# Adafruit_IS31FL3731_CharliePlex_Grid.net
KiCad netlist of a schematic drawn in EAGLE
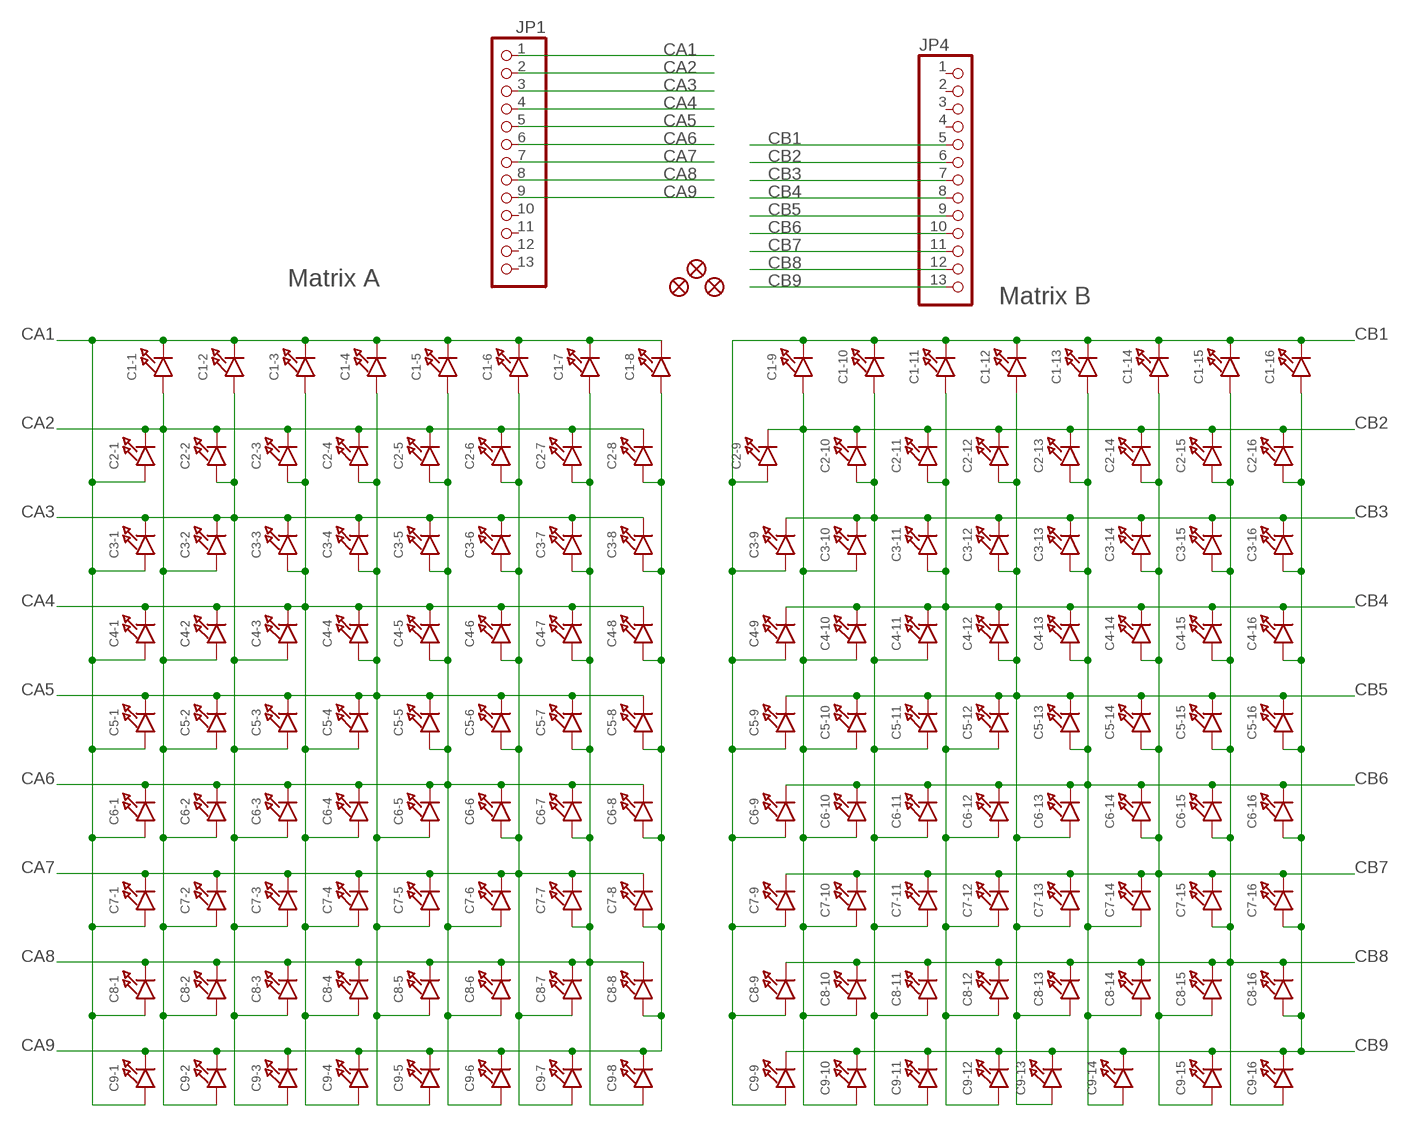
[diagram p0: schematic, sheet 1]

(export (version "E")
  (design (tool "Eeschema 10.0.6"))
  (components
    (comp (ref "C1-1")
      (value "LED0603_NOOUTLINE")
      (footprint "eagle-import:CHIPLED_0603_NOOUTLINE")
      (libsource (lib "eagle-import") (part "LED0603_NOOUTLINE"))
    )
    (comp (ref "C1-2")
      (value "LED0603_NOOUTLINE")
      (footprint "eagle-import:CHIPLED_0603_NOOUTLINE")
      (libsource (lib "eagle-import") (part "LED0603_NOOUTLINE"))
    )
    (comp (ref "C1-3")
      (value "LED0603_NOOUTLINE")
      (footprint "eagle-import:CHIPLED_0603_NOOUTLINE")
      (libsource (lib "eagle-import") (part "LED0603_NOOUTLINE"))
    )
    (comp (ref "C1-4")
      (value "LED0603_NOOUTLINE")
      (footprint "eagle-import:CHIPLED_0603_NOOUTLINE")
      (libsource (lib "eagle-import") (part "LED0603_NOOUTLINE"))
    )
    (comp (ref "C1-5")
      (value "LED0603_NOOUTLINE")
      (footprint "eagle-import:CHIPLED_0603_NOOUTLINE")
      (libsource (lib "eagle-import") (part "LED0603_NOOUTLINE"))
    )
    (comp (ref "C1-6")
      (value "LED0603_NOOUTLINE")
      (footprint "eagle-import:CHIPLED_0603_NOOUTLINE")
      (libsource (lib "eagle-import") (part "LED0603_NOOUTLINE"))
    )
    (comp (ref "C1-7")
      (value "LED0603_NOOUTLINE")
      (footprint "eagle-import:CHIPLED_0603_NOOUTLINE")
      (libsource (lib "eagle-import") (part "LED0603_NOOUTLINE"))
    )
    (comp (ref "C1-8")
      (value "LED0603_NOOUTLINE")
      (footprint "eagle-import:CHIPLED_0603_NOOUTLINE")
      (libsource (lib "eagle-import") (part "LED0603_NOOUTLINE"))
    )
    (comp (ref "C1-9")
      (value "LED0603_NOOUTLINE")
      (footprint "eagle-import:CHIPLED_0603_NOOUTLINE")
      (libsource (lib "eagle-import") (part "LED0603_NOOUTLINE"))
    )
    (comp (ref "C1-10")
      (value "LED0603_NOOUTLINE")
      (footprint "eagle-import:CHIPLED_0603_NOOUTLINE")
      (libsource (lib "eagle-import") (part "LED0603_NOOUTLINE"))
    )
    (comp (ref "C1-11")
      (value "LED0603_NOOUTLINE")
      (footprint "eagle-import:CHIPLED_0603_NOOUTLINE")
      (libsource (lib "eagle-import") (part "LED0603_NOOUTLINE"))
    )
    (comp (ref "C1-12")
      (value "LED0603_NOOUTLINE")
      (footprint "eagle-import:CHIPLED_0603_NOOUTLINE")
      (libsource (lib "eagle-import") (part "LED0603_NOOUTLINE"))
    )
    (comp (ref "C1-13")
      (value "LED0603_NOOUTLINE")
      (footprint "eagle-import:CHIPLED_0603_NOOUTLINE")
      (libsource (lib "eagle-import") (part "LED0603_NOOUTLINE"))
    )
    (comp (ref "C1-14")
      (value "LED0603_NOOUTLINE")
      (footprint "eagle-import:CHIPLED_0603_NOOUTLINE")
      (libsource (lib "eagle-import") (part "LED0603_NOOUTLINE"))
    )
    (comp (ref "C1-15")
      (value "LED0603_NOOUTLINE")
      (footprint "eagle-import:CHIPLED_0603_NOOUTLINE")
      (libsource (lib "eagle-import") (part "LED0603_NOOUTLINE"))
    )
    (comp (ref "C1-16")
      (value "LED0603_NOOUTLINE")
      (footprint "eagle-import:CHIPLED_0603_NOOUTLINE")
      (libsource (lib "eagle-import") (part "LED0603_NOOUTLINE"))
    )
    (comp (ref "C2-1")
      (value "LED0603_NOOUTLINE")
      (footprint "eagle-import:CHIPLED_0603_NOOUTLINE")
      (libsource (lib "eagle-import") (part "LED0603_NOOUTLINE"))
    )
    (comp (ref "C2-2")
      (value "LED0603_NOOUTLINE")
      (footprint "eagle-import:CHIPLED_0603_NOOUTLINE")
      (libsource (lib "eagle-import") (part "LED0603_NOOUTLINE"))
    )
    (comp (ref "C2-3")
      (value "LED0603_NOOUTLINE")
      (footprint "eagle-import:CHIPLED_0603_NOOUTLINE")
      (libsource (lib "eagle-import") (part "LED0603_NOOUTLINE"))
    )
    (comp (ref "C2-4")
      (value "LED0603_NOOUTLINE")
      (footprint "eagle-import:CHIPLED_0603_NOOUTLINE")
      (libsource (lib "eagle-import") (part "LED0603_NOOUTLINE"))
    )
    (comp (ref "C2-5")
      (value "LED0603_NOOUTLINE")
      (footprint "eagle-import:CHIPLED_0603_NOOUTLINE")
      (libsource (lib "eagle-import") (part "LED0603_NOOUTLINE"))
    )
    (comp (ref "C2-6")
      (value "LED0603_NOOUTLINE")
      (footprint "eagle-import:CHIPLED_0603_NOOUTLINE")
      (libsource (lib "eagle-import") (part "LED0603_NOOUTLINE"))
    )
    (comp (ref "C2-7")
      (value "LED0603_NOOUTLINE")
      (footprint "eagle-import:CHIPLED_0603_NOOUTLINE")
      (libsource (lib "eagle-import") (part "LED0603_NOOUTLINE"))
    )
    (comp (ref "C2-8")
      (value "LED0603_NOOUTLINE")
      (footprint "eagle-import:CHIPLED_0603_NOOUTLINE")
      (libsource (lib "eagle-import") (part "LED0603_NOOUTLINE"))
    )
    (comp (ref "C2-9")
      (value "LED0603_NOOUTLINE")
      (footprint "eagle-import:CHIPLED_0603_NOOUTLINE")
      (libsource (lib "eagle-import") (part "LED0603_NOOUTLINE"))
    )
    (comp (ref "C2-10")
      (value "LED0603_NOOUTLINE")
      (footprint "eagle-import:CHIPLED_0603_NOOUTLINE")
      (libsource (lib "eagle-import") (part "LED0603_NOOUTLINE"))
    )
    (comp (ref "C2-11")
      (value "LED0603_NOOUTLINE")
      (footprint "eagle-import:CHIPLED_0603_NOOUTLINE")
      (libsource (lib "eagle-import") (part "LED0603_NOOUTLINE"))
    )
    (comp (ref "C2-12")
      (value "LED0603_NOOUTLINE")
      (footprint "eagle-import:CHIPLED_0603_NOOUTLINE")
      (libsource (lib "eagle-import") (part "LED0603_NOOUTLINE"))
    )
    (comp (ref "C2-13")
      (value "LED0603_NOOUTLINE")
      (footprint "eagle-import:CHIPLED_0603_NOOUTLINE")
      (libsource (lib "eagle-import") (part "LED0603_NOOUTLINE"))
    )
    (comp (ref "C2-14")
      (value "LED0603_NOOUTLINE")
      (footprint "eagle-import:CHIPLED_0603_NOOUTLINE")
      (libsource (lib "eagle-import") (part "LED0603_NOOUTLINE"))
    )
    (comp (ref "C2-15")
      (value "LED0603_NOOUTLINE")
      (footprint "eagle-import:CHIPLED_0603_NOOUTLINE")
      (libsource (lib "eagle-import") (part "LED0603_NOOUTLINE"))
    )
    (comp (ref "C2-16")
      (value "LED0603_NOOUTLINE")
      (footprint "eagle-import:CHIPLED_0603_NOOUTLINE")
      (libsource (lib "eagle-import") (part "LED0603_NOOUTLINE"))
    )
    (comp (ref "C3-1")
      (value "LED0603_NOOUTLINE")
      (footprint "eagle-import:CHIPLED_0603_NOOUTLINE")
      (libsource (lib "eagle-import") (part "LED0603_NOOUTLINE"))
    )
    (comp (ref "C3-2")
      (value "LED0603_NOOUTLINE")
      (footprint "eagle-import:CHIPLED_0603_NOOUTLINE")
      (libsource (lib "eagle-import") (part "LED0603_NOOUTLINE"))
    )
    (comp (ref "C3-3")
      (value "LED0603_NOOUTLINE")
      (footprint "eagle-import:CHIPLED_0603_NOOUTLINE")
      (libsource (lib "eagle-import") (part "LED0603_NOOUTLINE"))
    )
    (comp (ref "C3-4")
      (value "LED0603_NOOUTLINE")
      (footprint "eagle-import:CHIPLED_0603_NOOUTLINE")
      (libsource (lib "eagle-import") (part "LED0603_NOOUTLINE"))
    )
    (comp (ref "C3-5")
      (value "LED0603_NOOUTLINE")
      (footprint "eagle-import:CHIPLED_0603_NOOUTLINE")
      (libsource (lib "eagle-import") (part "LED0603_NOOUTLINE"))
    )
    (comp (ref "C3-6")
      (value "LED0603_NOOUTLINE")
      (footprint "eagle-import:CHIPLED_0603_NOOUTLINE")
      (libsource (lib "eagle-import") (part "LED0603_NOOUTLINE"))
    )
    (comp (ref "C3-7")
      (value "LED0603_NOOUTLINE")
      (footprint "eagle-import:CHIPLED_0603_NOOUTLINE")
      (libsource (lib "eagle-import") (part "LED0603_NOOUTLINE"))
    )
    (comp (ref "C3-8")
      (value "LED0603_NOOUTLINE")
      (footprint "eagle-import:CHIPLED_0603_NOOUTLINE")
      (libsource (lib "eagle-import") (part "LED0603_NOOUTLINE"))
    )
    (comp (ref "C3-9")
      (value "LED0603_NOOUTLINE")
      (footprint "eagle-import:CHIPLED_0603_NOOUTLINE")
      (libsource (lib "eagle-import") (part "LED0603_NOOUTLINE"))
    )
    (comp (ref "C3-10")
      (value "LED0603_NOOUTLINE")
      (footprint "eagle-import:CHIPLED_0603_NOOUTLINE")
      (libsource (lib "eagle-import") (part "LED0603_NOOUTLINE"))
    )
    (comp (ref "C3-11")
      (value "LED0603_NOOUTLINE")
      (footprint "eagle-import:CHIPLED_0603_NOOUTLINE")
      (libsource (lib "eagle-import") (part "LED0603_NOOUTLINE"))
    )
    (comp (ref "C3-12")
      (value "LED0603_NOOUTLINE")
      (footprint "eagle-import:CHIPLED_0603_NOOUTLINE")
      (libsource (lib "eagle-import") (part "LED0603_NOOUTLINE"))
    )
    (comp (ref "C3-13")
      (value "LED0603_NOOUTLINE")
      (footprint "eagle-import:CHIPLED_0603_NOOUTLINE")
      (libsource (lib "eagle-import") (part "LED0603_NOOUTLINE"))
    )
    (comp (ref "C3-14")
      (value "LED0603_NOOUTLINE")
      (footprint "eagle-import:CHIPLED_0603_NOOUTLINE")
      (libsource (lib "eagle-import") (part "LED0603_NOOUTLINE"))
    )
    (comp (ref "C3-15")
      (value "LED0603_NOOUTLINE")
      (footprint "eagle-import:CHIPLED_0603_NOOUTLINE")
      (libsource (lib "eagle-import") (part "LED0603_NOOUTLINE"))
    )
    (comp (ref "C3-16")
      (value "LED0603_NOOUTLINE")
      (footprint "eagle-import:CHIPLED_0603_NOOUTLINE")
      (libsource (lib "eagle-import") (part "LED0603_NOOUTLINE"))
    )
    (comp (ref "C4-1")
      (value "LED0603_NOOUTLINE")
      (footprint "eagle-import:CHIPLED_0603_NOOUTLINE")
      (libsource (lib "eagle-import") (part "LED0603_NOOUTLINE"))
    )
    (comp (ref "C4-2")
      (value "LED0603_NOOUTLINE")
      (footprint "eagle-import:CHIPLED_0603_NOOUTLINE")
      (libsource (lib "eagle-import") (part "LED0603_NOOUTLINE"))
    )
    (comp (ref "C4-3")
      (value "LED0603_NOOUTLINE")
      (footprint "eagle-import:CHIPLED_0603_NOOUTLINE")
      (libsource (lib "eagle-import") (part "LED0603_NOOUTLINE"))
    )
    (comp (ref "C4-4")
      (value "LED0603_NOOUTLINE")
      (footprint "eagle-import:CHIPLED_0603_NOOUTLINE")
      (libsource (lib "eagle-import") (part "LED0603_NOOUTLINE"))
    )
    (comp (ref "C4-5")
      (value "LED0603_NOOUTLINE")
      (footprint "eagle-import:CHIPLED_0603_NOOUTLINE")
      (libsource (lib "eagle-import") (part "LED0603_NOOUTLINE"))
    )
    (comp (ref "C4-6")
      (value "LED0603_NOOUTLINE")
      (footprint "eagle-import:CHIPLED_0603_NOOUTLINE")
      (libsource (lib "eagle-import") (part "LED0603_NOOUTLINE"))
    )
    (comp (ref "C4-7")
      (value "LED0603_NOOUTLINE")
      (footprint "eagle-import:CHIPLED_0603_NOOUTLINE")
      (libsource (lib "eagle-import") (part "LED0603_NOOUTLINE"))
    )
    (comp (ref "C4-8")
      (value "LED0603_NOOUTLINE")
      (footprint "eagle-import:CHIPLED_0603_NOOUTLINE")
      (libsource (lib "eagle-import") (part "LED0603_NOOUTLINE"))
    )
    (comp (ref "C4-9")
      (value "LED0603_NOOUTLINE")
      (footprint "eagle-import:CHIPLED_0603_NOOUTLINE")
      (libsource (lib "eagle-import") (part "LED0603_NOOUTLINE"))
    )
    (comp (ref "C4-10")
      (value "LED0603_NOOUTLINE")
      (footprint "eagle-import:CHIPLED_0603_NOOUTLINE")
      (libsource (lib "eagle-import") (part "LED0603_NOOUTLINE"))
    )
    (comp (ref "C4-11")
      (value "LED0603_NOOUTLINE")
      (footprint "eagle-import:CHIPLED_0603_NOOUTLINE")
      (libsource (lib "eagle-import") (part "LED0603_NOOUTLINE"))
    )
    (comp (ref "C4-12")
      (value "LED0603_NOOUTLINE")
      (footprint "eagle-import:CHIPLED_0603_NOOUTLINE")
      (libsource (lib "eagle-import") (part "LED0603_NOOUTLINE"))
    )
    (comp (ref "C4-13")
      (value "LED0603_NOOUTLINE")
      (footprint "eagle-import:CHIPLED_0603_NOOUTLINE")
      (libsource (lib "eagle-import") (part "LED0603_NOOUTLINE"))
    )
    (comp (ref "C4-14")
      (value "LED0603_NOOUTLINE")
      (footprint "eagle-import:CHIPLED_0603_NOOUTLINE")
      (libsource (lib "eagle-import") (part "LED0603_NOOUTLINE"))
    )
    (comp (ref "C4-15")
      (value "LED0603_NOOUTLINE")
      (footprint "eagle-import:CHIPLED_0603_NOOUTLINE")
      (libsource (lib "eagle-import") (part "LED0603_NOOUTLINE"))
    )
    (comp (ref "C4-16")
      (value "LED0603_NOOUTLINE")
      (footprint "eagle-import:CHIPLED_0603_NOOUTLINE")
      (libsource (lib "eagle-import") (part "LED0603_NOOUTLINE"))
    )
    (comp (ref "C5-1")
      (value "LED0603_NOOUTLINE")
      (footprint "eagle-import:CHIPLED_0603_NOOUTLINE")
      (libsource (lib "eagle-import") (part "LED0603_NOOUTLINE"))
    )
    (comp (ref "C5-2")
      (value "LED0603_NOOUTLINE")
      (footprint "eagle-import:CHIPLED_0603_NOOUTLINE")
      (libsource (lib "eagle-import") (part "LED0603_NOOUTLINE"))
    )
    (comp (ref "C5-3")
      (value "LED0603_NOOUTLINE")
      (footprint "eagle-import:CHIPLED_0603_NOOUTLINE")
      (libsource (lib "eagle-import") (part "LED0603_NOOUTLINE"))
    )
    (comp (ref "C5-4")
      (value "LED0603_NOOUTLINE")
      (footprint "eagle-import:CHIPLED_0603_NOOUTLINE")
      (libsource (lib "eagle-import") (part "LED0603_NOOUTLINE"))
    )
    (comp (ref "C5-5")
      (value "LED0603_NOOUTLINE")
      (footprint "eagle-import:CHIPLED_0603_NOOUTLINE")
      (libsource (lib "eagle-import") (part "LED0603_NOOUTLINE"))
    )
    (comp (ref "C5-6")
      (value "LED0603_NOOUTLINE")
      (footprint "eagle-import:CHIPLED_0603_NOOUTLINE")
      (libsource (lib "eagle-import") (part "LED0603_NOOUTLINE"))
    )
    (comp (ref "C5-7")
      (value "LED0603_NOOUTLINE")
      (footprint "eagle-import:CHIPLED_0603_NOOUTLINE")
      (libsource (lib "eagle-import") (part "LED0603_NOOUTLINE"))
    )
    (comp (ref "C5-8")
      (value "LED0603_NOOUTLINE")
      (footprint "eagle-import:CHIPLED_0603_NOOUTLINE")
      (libsource (lib "eagle-import") (part "LED0603_NOOUTLINE"))
    )
    (comp (ref "C5-9")
      (value "LED0603_NOOUTLINE")
      (footprint "eagle-import:CHIPLED_0603_NOOUTLINE")
      (libsource (lib "eagle-import") (part "LED0603_NOOUTLINE"))
    )
    (comp (ref "C5-10")
      (value "LED0603_NOOUTLINE")
      (footprint "eagle-import:CHIPLED_0603_NOOUTLINE")
      (libsource (lib "eagle-import") (part "LED0603_NOOUTLINE"))
    )
    (comp (ref "C5-11")
      (value "LED0603_NOOUTLINE")
      (footprint "eagle-import:CHIPLED_0603_NOOUTLINE")
      (libsource (lib "eagle-import") (part "LED0603_NOOUTLINE"))
    )
    (comp (ref "C5-12")
      (value "LED0603_NOOUTLINE")
      (footprint "eagle-import:CHIPLED_0603_NOOUTLINE")
      (libsource (lib "eagle-import") (part "LED0603_NOOUTLINE"))
    )
    (comp (ref "C5-13")
      (value "LED0603_NOOUTLINE")
      (footprint "eagle-import:CHIPLED_0603_NOOUTLINE")
      (libsource (lib "eagle-import") (part "LED0603_NOOUTLINE"))
    )
    (comp (ref "C5-14")
      (value "LED0603_NOOUTLINE")
      (footprint "eagle-import:CHIPLED_0603_NOOUTLINE")
      (libsource (lib "eagle-import") (part "LED0603_NOOUTLINE"))
    )
    (comp (ref "C5-15")
      (value "LED0603_NOOUTLINE")
      (footprint "eagle-import:CHIPLED_0603_NOOUTLINE")
      (libsource (lib "eagle-import") (part "LED0603_NOOUTLINE"))
    )
    (comp (ref "C5-16")
      (value "LED0603_NOOUTLINE")
      (footprint "eagle-import:CHIPLED_0603_NOOUTLINE")
      (libsource (lib "eagle-import") (part "LED0603_NOOUTLINE"))
    )
    (comp (ref "C6-1")
      (value "LED0603_NOOUTLINE")
      (footprint "eagle-import:CHIPLED_0603_NOOUTLINE")
      (libsource (lib "eagle-import") (part "LED0603_NOOUTLINE"))
    )
    (comp (ref "C6-2")
      (value "LED0603_NOOUTLINE")
      (footprint "eagle-import:CHIPLED_0603_NOOUTLINE")
      (libsource (lib "eagle-import") (part "LED0603_NOOUTLINE"))
    )
    (comp (ref "C6-3")
      (value "LED0603_NOOUTLINE")
      (footprint "eagle-import:CHIPLED_0603_NOOUTLINE")
      (libsource (lib "eagle-import") (part "LED0603_NOOUTLINE"))
    )
    (comp (ref "C6-4")
      (value "LED0603_NOOUTLINE")
      (footprint "eagle-import:CHIPLED_0603_NOOUTLINE")
      (libsource (lib "eagle-import") (part "LED0603_NOOUTLINE"))
    )
    (comp (ref "C6-5")
      (value "LED0603_NOOUTLINE")
      (footprint "eagle-import:CHIPLED_0603_NOOUTLINE")
      (libsource (lib "eagle-import") (part "LED0603_NOOUTLINE"))
    )
    (comp (ref "C6-6")
      (value "LED0603_NOOUTLINE")
      (footprint "eagle-import:CHIPLED_0603_NOOUTLINE")
      (libsource (lib "eagle-import") (part "LED0603_NOOUTLINE"))
    )
    (comp (ref "C6-7")
      (value "LED0603_NOOUTLINE")
      (footprint "eagle-import:CHIPLED_0603_NOOUTLINE")
      (libsource (lib "eagle-import") (part "LED0603_NOOUTLINE"))
    )
    (comp (ref "C6-8")
      (value "LED0603_NOOUTLINE")
      (footprint "eagle-import:CHIPLED_0603_NOOUTLINE")
      (libsource (lib "eagle-import") (part "LED0603_NOOUTLINE"))
    )
    (comp (ref "C6-9")
      (value "LED0603_NOOUTLINE")
      (footprint "eagle-import:CHIPLED_0603_NOOUTLINE")
      (libsource (lib "eagle-import") (part "LED0603_NOOUTLINE"))
    )
    (comp (ref "C6-10")
      (value "LED0603_NOOUTLINE")
      (footprint "eagle-import:CHIPLED_0603_NOOUTLINE")
      (libsource (lib "eagle-import") (part "LED0603_NOOUTLINE"))
    )
    (comp (ref "C6-11")
      (value "LED0603_NOOUTLINE")
      (footprint "eagle-import:CHIPLED_0603_NOOUTLINE")
      (libsource (lib "eagle-import") (part "LED0603_NOOUTLINE"))
    )
    (comp (ref "C6-12")
      (value "LED0603_NOOUTLINE")
      (footprint "eagle-import:CHIPLED_0603_NOOUTLINE")
      (libsource (lib "eagle-import") (part "LED0603_NOOUTLINE"))
    )
    (comp (ref "C6-13")
      (value "LED0603_NOOUTLINE")
      (footprint "eagle-import:CHIPLED_0603_NOOUTLINE")
      (libsource (lib "eagle-import") (part "LED0603_NOOUTLINE"))
    )
    (comp (ref "C6-14")
      (value "LED0603_NOOUTLINE")
      (footprint "eagle-import:CHIPLED_0603_NOOUTLINE")
      (libsource (lib "eagle-import") (part "LED0603_NOOUTLINE"))
    )
    (comp (ref "C6-15")
      (value "LED0603_NOOUTLINE")
      (footprint "eagle-import:CHIPLED_0603_NOOUTLINE")
      (libsource (lib "eagle-import") (part "LED0603_NOOUTLINE"))
    )
    (comp (ref "C6-16")
      (value "LED0603_NOOUTLINE")
      (footprint "eagle-import:CHIPLED_0603_NOOUTLINE")
      (libsource (lib "eagle-import") (part "LED0603_NOOUTLINE"))
    )
    (comp (ref "C7-1")
      (value "LED0603_NOOUTLINE")
      (footprint "eagle-import:CHIPLED_0603_NOOUTLINE")
      (libsource (lib "eagle-import") (part "LED0603_NOOUTLINE"))
    )
    (comp (ref "C7-2")
      (value "LED0603_NOOUTLINE")
      (footprint "eagle-import:CHIPLED_0603_NOOUTLINE")
      (libsource (lib "eagle-import") (part "LED0603_NOOUTLINE"))
    )
    (comp (ref "C7-3")
      (value "LED0603_NOOUTLINE")
      (footprint "eagle-import:CHIPLED_0603_NOOUTLINE")
      (libsource (lib "eagle-import") (part "LED0603_NOOUTLINE"))
    )
    (comp (ref "C7-4")
      (value "LED0603_NOOUTLINE")
      (footprint "eagle-import:CHIPLED_0603_NOOUTLINE")
      (libsource (lib "eagle-import") (part "LED0603_NOOUTLINE"))
    )
    (comp (ref "C7-5")
      (value "LED0603_NOOUTLINE")
      (footprint "eagle-import:CHIPLED_0603_NOOUTLINE")
      (libsource (lib "eagle-import") (part "LED0603_NOOUTLINE"))
    )
    (comp (ref "C7-6")
      (value "LED0603_NOOUTLINE")
      (footprint "eagle-import:CHIPLED_0603_NOOUTLINE")
      (libsource (lib "eagle-import") (part "LED0603_NOOUTLINE"))
    )
    (comp (ref "C7-7")
      (value "LED0603_NOOUTLINE")
      (footprint "eagle-import:CHIPLED_0603_NOOUTLINE")
      (libsource (lib "eagle-import") (part "LED0603_NOOUTLINE"))
    )
    (comp (ref "C7-8")
      (value "LED0603_NOOUTLINE")
      (footprint "eagle-import:CHIPLED_0603_NOOUTLINE")
      (libsource (lib "eagle-import") (part "LED0603_NOOUTLINE"))
    )
    (comp (ref "C7-9")
      (value "LED0603_NOOUTLINE")
      (footprint "eagle-import:CHIPLED_0603_NOOUTLINE")
      (libsource (lib "eagle-import") (part "LED0603_NOOUTLINE"))
    )
    (comp (ref "C7-10")
      (value "LED0603_NOOUTLINE")
      (footprint "eagle-import:CHIPLED_0603_NOOUTLINE")
      (libsource (lib "eagle-import") (part "LED0603_NOOUTLINE"))
    )
    (comp (ref "C7-11")
      (value "LED0603_NOOUTLINE")
      (footprint "eagle-import:CHIPLED_0603_NOOUTLINE")
      (libsource (lib "eagle-import") (part "LED0603_NOOUTLINE"))
    )
    (comp (ref "C7-12")
      (value "LED0603_NOOUTLINE")
      (footprint "eagle-import:CHIPLED_0603_NOOUTLINE")
      (libsource (lib "eagle-import") (part "LED0603_NOOUTLINE"))
    )
    (comp (ref "C7-13")
      (value "LED0603_NOOUTLINE")
      (footprint "eagle-import:CHIPLED_0603_NOOUTLINE")
      (libsource (lib "eagle-import") (part "LED0603_NOOUTLINE"))
    )
    (comp (ref "C7-14")
      (value "LED0603_NOOUTLINE")
      (footprint "eagle-import:CHIPLED_0603_NOOUTLINE")
      (libsource (lib "eagle-import") (part "LED0603_NOOUTLINE"))
    )
    (comp (ref "C7-15")
      (value "LED0603_NOOUTLINE")
      (footprint "eagle-import:CHIPLED_0603_NOOUTLINE")
      (libsource (lib "eagle-import") (part "LED0603_NOOUTLINE"))
    )
    (comp (ref "C7-16")
      (value "LED0603_NOOUTLINE")
      (footprint "eagle-import:CHIPLED_0603_NOOUTLINE")
      (libsource (lib "eagle-import") (part "LED0603_NOOUTLINE"))
    )
    (comp (ref "C8-1")
      (value "LED0603_NOOUTLINE")
      (footprint "eagle-import:CHIPLED_0603_NOOUTLINE")
      (libsource (lib "eagle-import") (part "LED0603_NOOUTLINE"))
    )
    (comp (ref "C8-2")
      (value "LED0603_NOOUTLINE")
      (footprint "eagle-import:CHIPLED_0603_NOOUTLINE")
      (libsource (lib "eagle-import") (part "LED0603_NOOUTLINE"))
    )
    (comp (ref "C8-3")
      (value "LED0603_NOOUTLINE")
      (footprint "eagle-import:CHIPLED_0603_NOOUTLINE")
      (libsource (lib "eagle-import") (part "LED0603_NOOUTLINE"))
    )
    (comp (ref "C8-4")
      (value "LED0603_NOOUTLINE")
      (footprint "eagle-import:CHIPLED_0603_NOOUTLINE")
      (libsource (lib "eagle-import") (part "LED0603_NOOUTLINE"))
    )
    (comp (ref "C8-5")
      (value "LED0603_NOOUTLINE")
      (footprint "eagle-import:CHIPLED_0603_NOOUTLINE")
      (libsource (lib "eagle-import") (part "LED0603_NOOUTLINE"))
    )
    (comp (ref "C8-6")
      (value "LED0603_NOOUTLINE")
      (footprint "eagle-import:CHIPLED_0603_NOOUTLINE")
      (libsource (lib "eagle-import") (part "LED0603_NOOUTLINE"))
    )
    (comp (ref "C8-7")
      (value "LED0603_NOOUTLINE")
      (footprint "eagle-import:CHIPLED_0603_NOOUTLINE")
      (libsource (lib "eagle-import") (part "LED0603_NOOUTLINE"))
    )
    (comp (ref "C8-8")
      (value "LED0603_NOOUTLINE")
      (footprint "eagle-import:CHIPLED_0603_NOOUTLINE")
      (libsource (lib "eagle-import") (part "LED0603_NOOUTLINE"))
    )
    (comp (ref "C8-9")
      (value "LED0603_NOOUTLINE")
      (footprint "eagle-import:CHIPLED_0603_NOOUTLINE")
      (libsource (lib "eagle-import") (part "LED0603_NOOUTLINE"))
    )
    (comp (ref "C8-10")
      (value "LED0603_NOOUTLINE")
      (footprint "eagle-import:CHIPLED_0603_NOOUTLINE")
      (libsource (lib "eagle-import") (part "LED0603_NOOUTLINE"))
    )
    (comp (ref "C8-11")
      (value "LED0603_NOOUTLINE")
      (footprint "eagle-import:CHIPLED_0603_NOOUTLINE")
      (libsource (lib "eagle-import") (part "LED0603_NOOUTLINE"))
    )
    (comp (ref "C8-12")
      (value "LED0603_NOOUTLINE")
      (footprint "eagle-import:CHIPLED_0603_NOOUTLINE")
      (libsource (lib "eagle-import") (part "LED0603_NOOUTLINE"))
    )
    (comp (ref "C8-13")
      (value "LED0603_NOOUTLINE")
      (footprint "eagle-import:CHIPLED_0603_NOOUTLINE")
      (libsource (lib "eagle-import") (part "LED0603_NOOUTLINE"))
    )
    (comp (ref "C8-14")
      (value "LED0603_NOOUTLINE")
      (footprint "eagle-import:CHIPLED_0603_NOOUTLINE")
      (libsource (lib "eagle-import") (part "LED0603_NOOUTLINE"))
    )
    (comp (ref "C8-15")
      (value "LED0603_NOOUTLINE")
      (footprint "eagle-import:CHIPLED_0603_NOOUTLINE")
      (libsource (lib "eagle-import") (part "LED0603_NOOUTLINE"))
    )
    (comp (ref "C8-16")
      (value "LED0603_NOOUTLINE")
      (footprint "eagle-import:CHIPLED_0603_NOOUTLINE")
      (libsource (lib "eagle-import") (part "LED0603_NOOUTLINE"))
    )
    (comp (ref "C9-1")
      (value "LED0603_NOOUTLINE")
      (footprint "eagle-import:CHIPLED_0603_NOOUTLINE")
      (libsource (lib "eagle-import") (part "LED0603_NOOUTLINE"))
    )
    (comp (ref "C9-2")
      (value "LED0603_NOOUTLINE")
      (footprint "eagle-import:CHIPLED_0603_NOOUTLINE")
      (libsource (lib "eagle-import") (part "LED0603_NOOUTLINE"))
    )
    (comp (ref "C9-3")
      (value "LED0603_NOOUTLINE")
      (footprint "eagle-import:CHIPLED_0603_NOOUTLINE")
      (libsource (lib "eagle-import") (part "LED0603_NOOUTLINE"))
    )
    (comp (ref "C9-4")
      (value "LED0603_NOOUTLINE")
      (footprint "eagle-import:CHIPLED_0603_NOOUTLINE")
      (libsource (lib "eagle-import") (part "LED0603_NOOUTLINE"))
    )
    (comp (ref "C9-5")
      (value "LED0603_NOOUTLINE")
      (footprint "eagle-import:CHIPLED_0603_NOOUTLINE")
      (libsource (lib "eagle-import") (part "LED0603_NOOUTLINE"))
    )
    (comp (ref "C9-6")
      (value "LED0603_NOOUTLINE")
      (footprint "eagle-import:CHIPLED_0603_NOOUTLINE")
      (libsource (lib "eagle-import") (part "LED0603_NOOUTLINE"))
    )
    (comp (ref "C9-7")
      (value "LED0603_NOOUTLINE")
      (footprint "eagle-import:CHIPLED_0603_NOOUTLINE")
      (libsource (lib "eagle-import") (part "LED0603_NOOUTLINE"))
    )
    (comp (ref "C9-8")
      (value "LED0603_NOOUTLINE")
      (footprint "eagle-import:CHIPLED_0603_NOOUTLINE")
      (libsource (lib "eagle-import") (part "LED0603_NOOUTLINE"))
    )
    (comp (ref "C9-9")
      (value "LED0603_NOOUTLINE")
      (footprint "eagle-import:CHIPLED_0603_NOOUTLINE")
      (libsource (lib "eagle-import") (part "LED0603_NOOUTLINE"))
    )
    (comp (ref "C9-10")
      (value "LED0603_NOOUTLINE")
      (footprint "eagle-import:CHIPLED_0603_NOOUTLINE")
      (libsource (lib "eagle-import") (part "LED0603_NOOUTLINE"))
    )
    (comp (ref "C9-11")
      (value "LED0603_NOOUTLINE")
      (footprint "eagle-import:CHIPLED_0603_NOOUTLINE")
      (libsource (lib "eagle-import") (part "LED0603_NOOUTLINE"))
    )
    (comp (ref "C9-12")
      (value "LED0603_NOOUTLINE")
      (footprint "eagle-import:CHIPLED_0603_NOOUTLINE")
      (libsource (lib "eagle-import") (part "LED0603_NOOUTLINE"))
    )
    (comp (ref "C9-13")
      (value "LED0603_NOOUTLINE")
      (footprint "eagle-import:CHIPLED_0603_NOOUTLINE")
      (libsource (lib "eagle-import") (part "LED0603_NOOUTLINE"))
    )
    (comp (ref "C9-14")
      (value "LED0603_NOOUTLINE")
      (footprint "eagle-import:CHIPLED_0603_NOOUTLINE")
      (libsource (lib "eagle-import") (part "LED0603_NOOUTLINE"))
    )
    (comp (ref "C9-15")
      (value "LED0603_NOOUTLINE")
      (footprint "eagle-import:CHIPLED_0603_NOOUTLINE")
      (libsource (lib "eagle-import") (part "LED0603_NOOUTLINE"))
    )
    (comp (ref "C9-16")
      (value "LED0603_NOOUTLINE")
      (footprint "eagle-import:CHIPLED_0603_NOOUTLINE")
      (libsource (lib "eagle-import") (part "LED0603_NOOUTLINE"))
    )
    (comp (ref "FID1")
      (value "FIDUCIAL\"\"")
      (footprint "eagle-import:FIDUCIAL_1MM")
      (libsource (lib "eagle-import") (part "FIDUCIAL{dblquote}{dblquote}"))
    )
    (comp (ref "FID2")
      (value "FIDUCIAL\"\"")
      (footprint "eagle-import:FIDUCIAL_1MM")
      (libsource (lib "eagle-import") (part "FIDUCIAL{dblquote}{dblquote}"))
    )
    (comp (ref "FID3")
      (value "FIDUCIAL\"\"")
      (footprint "eagle-import:FIDUCIAL_1MM")
      (libsource (lib "eagle-import") (part "FIDUCIAL{dblquote}{dblquote}"))
    )
    (comp (ref "JP1")
      (value "HEADER-1X13")
      (footprint "eagle-import:1X13_ROUND_70")
      (libsource (lib "eagle-import") (part "HEADER-1X13"))
    )
    (comp (ref "JP4")
      (value "HEADER-1X13")
      (footprint "eagle-import:1X13_ROUND_70")
      (libsource (lib "eagle-import") (part "HEADER-1X13"))
    )
  )
  (nets
    (net (code "1") (name "/CA1") (class "Default")
      (node (ref "C1-1") (pin "C") (pinfunction "C_C") (pintype "passive"))
      (node (ref "C1-2") (pin "C") (pinfunction "C_C") (pintype "passive"))
      (node (ref "C1-3") (pin "C") (pinfunction "C_C") (pintype "passive"))
      (node (ref "C1-4") (pin "C") (pinfunction "C_C") (pintype "passive"))
      (node (ref "C1-5") (pin "C") (pinfunction "C_C") (pintype "passive"))
      (node (ref "C1-6") (pin "C") (pinfunction "C_C") (pintype "passive"))
      (node (ref "C1-7") (pin "C") (pinfunction "C_C") (pintype "passive"))
      (node (ref "C1-8") (pin "C") (pinfunction "C_C") (pintype "passive"))
      (node (ref "C2-1") (pin "A") (pinfunction "A_A") (pintype "passive"))
      (node (ref "C3-1") (pin "A") (pinfunction "A_A") (pintype "passive"))
      (node (ref "C4-1") (pin "A") (pinfunction "A_A") (pintype "passive"))
      (node (ref "C5-1") (pin "A") (pinfunction "A_A") (pintype "passive"))
      (node (ref "C6-1") (pin "A") (pinfunction "A_A") (pintype "passive"))
      (node (ref "C7-1") (pin "A") (pinfunction "A_A") (pintype "passive"))
      (node (ref "C8-1") (pin "A") (pinfunction "A_A") (pintype "passive"))
      (node (ref "C9-1") (pin "A") (pinfunction "A_A") (pintype "passive"))
      (node (ref "JP1") (pin "1") (pinfunction "1_1") (pintype "passive"))
    )
    (net (code "2") (name "/CA2") (class "Default")
      (node (ref "C1-1") (pin "A") (pinfunction "A_A") (pintype "passive"))
      (node (ref "C2-1") (pin "C") (pinfunction "C_C") (pintype "passive"))
      (node (ref "C2-2") (pin "C") (pinfunction "C_C") (pintype "passive"))
      (node (ref "C2-3") (pin "C") (pinfunction "C_C") (pintype "passive"))
      (node (ref "C2-4") (pin "C") (pinfunction "C_C") (pintype "passive"))
      (node (ref "C2-5") (pin "C") (pinfunction "C_C") (pintype "passive"))
      (node (ref "C2-6") (pin "C") (pinfunction "C_C") (pintype "passive"))
      (node (ref "C2-7") (pin "C") (pinfunction "C_C") (pintype "passive"))
      (node (ref "C2-8") (pin "C") (pinfunction "C_C") (pintype "passive"))
      (node (ref "C3-2") (pin "A") (pinfunction "A_A") (pintype "passive"))
      (node (ref "C4-2") (pin "A") (pinfunction "A_A") (pintype "passive"))
      (node (ref "C5-2") (pin "A") (pinfunction "A_A") (pintype "passive"))
      (node (ref "C6-2") (pin "A") (pinfunction "A_A") (pintype "passive"))
      (node (ref "C7-2") (pin "A") (pinfunction "A_A") (pintype "passive"))
      (node (ref "C8-2") (pin "A") (pinfunction "A_A") (pintype "passive"))
      (node (ref "C9-2") (pin "A") (pinfunction "A_A") (pintype "passive"))
      (node (ref "JP1") (pin "2") (pinfunction "2_2") (pintype "passive"))
    )
    (net (code "3") (name "/CA3") (class "Default")
      (node (ref "C1-2") (pin "A") (pinfunction "A_A") (pintype "passive"))
      (node (ref "C2-2") (pin "A") (pinfunction "A_A") (pintype "passive"))
      (node (ref "C3-1") (pin "C") (pinfunction "C_C") (pintype "passive"))
      (node (ref "C3-2") (pin "C") (pinfunction "C_C") (pintype "passive"))
      (node (ref "C3-3") (pin "C") (pinfunction "C_C") (pintype "passive"))
      (node (ref "C3-4") (pin "C") (pinfunction "C_C") (pintype "passive"))
      (node (ref "C3-5") (pin "C") (pinfunction "C_C") (pintype "passive"))
      (node (ref "C3-6") (pin "C") (pinfunction "C_C") (pintype "passive"))
      (node (ref "C3-7") (pin "C") (pinfunction "C_C") (pintype "passive"))
      (node (ref "C3-8") (pin "C") (pinfunction "C_C") (pintype "passive"))
      (node (ref "C4-3") (pin "A") (pinfunction "A_A") (pintype "passive"))
      (node (ref "C5-3") (pin "A") (pinfunction "A_A") (pintype "passive"))
      (node (ref "C6-3") (pin "A") (pinfunction "A_A") (pintype "passive"))
      (node (ref "C7-3") (pin "A") (pinfunction "A_A") (pintype "passive"))
      (node (ref "C8-3") (pin "A") (pinfunction "A_A") (pintype "passive"))
      (node (ref "C9-3") (pin "A") (pinfunction "A_A") (pintype "passive"))
      (node (ref "JP1") (pin "3") (pinfunction "3_3") (pintype "passive"))
    )
    (net (code "4") (name "/CA4") (class "Default")
      (node (ref "C1-3") (pin "A") (pinfunction "A_A") (pintype "passive"))
      (node (ref "C2-3") (pin "A") (pinfunction "A_A") (pintype "passive"))
      (node (ref "C3-3") (pin "A") (pinfunction "A_A") (pintype "passive"))
      (node (ref "C4-1") (pin "C") (pinfunction "C_C") (pintype "passive"))
      (node (ref "C4-2") (pin "C") (pinfunction "C_C") (pintype "passive"))
      (node (ref "C4-3") (pin "C") (pinfunction "C_C") (pintype "passive"))
      (node (ref "C4-4") (pin "C") (pinfunction "C_C") (pintype "passive"))
      (node (ref "C4-5") (pin "C") (pinfunction "C_C") (pintype "passive"))
      (node (ref "C4-6") (pin "C") (pinfunction "C_C") (pintype "passive"))
      (node (ref "C4-7") (pin "C") (pinfunction "C_C") (pintype "passive"))
      (node (ref "C4-8") (pin "C") (pinfunction "C_C") (pintype "passive"))
      (node (ref "C5-4") (pin "A") (pinfunction "A_A") (pintype "passive"))
      (node (ref "C6-4") (pin "A") (pinfunction "A_A") (pintype "passive"))
      (node (ref "C7-4") (pin "A") (pinfunction "A_A") (pintype "passive"))
      (node (ref "C8-4") (pin "A") (pinfunction "A_A") (pintype "passive"))
      (node (ref "C9-4") (pin "A") (pinfunction "A_A") (pintype "passive"))
      (node (ref "JP1") (pin "4") (pinfunction "4_4") (pintype "passive"))
    )
    (net (code "5") (name "/CA5") (class "Default")
      (node (ref "C1-4") (pin "A") (pinfunction "A_A") (pintype "passive"))
      (node (ref "C2-4") (pin "A") (pinfunction "A_A") (pintype "passive"))
      (node (ref "C3-4") (pin "A") (pinfunction "A_A") (pintype "passive"))
      (node (ref "C4-4") (pin "A") (pinfunction "A_A") (pintype "passive"))
      (node (ref "C5-1") (pin "C") (pinfunction "C_C") (pintype "passive"))
      (node (ref "C5-2") (pin "C") (pinfunction "C_C") (pintype "passive"))
      (node (ref "C5-3") (pin "C") (pinfunction "C_C") (pintype "passive"))
      (node (ref "C5-4") (pin "C") (pinfunction "C_C") (pintype "passive"))
      (node (ref "C5-5") (pin "C") (pinfunction "C_C") (pintype "passive"))
      (node (ref "C5-6") (pin "C") (pinfunction "C_C") (pintype "passive"))
      (node (ref "C5-7") (pin "C") (pinfunction "C_C") (pintype "passive"))
      (node (ref "C5-8") (pin "C") (pinfunction "C_C") (pintype "passive"))
      (node (ref "C6-5") (pin "A") (pinfunction "A_A") (pintype "passive"))
      (node (ref "C7-5") (pin "A") (pinfunction "A_A") (pintype "passive"))
      (node (ref "C8-5") (pin "A") (pinfunction "A_A") (pintype "passive"))
      (node (ref "C9-5") (pin "A") (pinfunction "A_A") (pintype "passive"))
      (node (ref "JP1") (pin "5") (pinfunction "5_5") (pintype "passive"))
    )
    (net (code "6") (name "/CA6") (class "Default")
      (node (ref "C1-5") (pin "A") (pinfunction "A_A") (pintype "passive"))
      (node (ref "C2-5") (pin "A") (pinfunction "A_A") (pintype "passive"))
      (node (ref "C3-5") (pin "A") (pinfunction "A_A") (pintype "passive"))
      (node (ref "C4-5") (pin "A") (pinfunction "A_A") (pintype "passive"))
      (node (ref "C5-5") (pin "A") (pinfunction "A_A") (pintype "passive"))
      (node (ref "C6-1") (pin "C") (pinfunction "C_C") (pintype "passive"))
      (node (ref "C6-2") (pin "C") (pinfunction "C_C") (pintype "passive"))
      (node (ref "C6-3") (pin "C") (pinfunction "C_C") (pintype "passive"))
      (node (ref "C6-4") (pin "C") (pinfunction "C_C") (pintype "passive"))
      (node (ref "C6-5") (pin "C") (pinfunction "C_C") (pintype "passive"))
      (node (ref "C6-6") (pin "C") (pinfunction "C_C") (pintype "passive"))
      (node (ref "C6-7") (pin "C") (pinfunction "C_C") (pintype "passive"))
      (node (ref "C6-8") (pin "C") (pinfunction "C_C") (pintype "passive"))
      (node (ref "C7-6") (pin "A") (pinfunction "A_A") (pintype "passive"))
      (node (ref "C8-6") (pin "A") (pinfunction "A_A") (pintype "passive"))
      (node (ref "C9-6") (pin "A") (pinfunction "A_A") (pintype "passive"))
      (node (ref "JP1") (pin "6") (pinfunction "6_6") (pintype "passive"))
    )
    (net (code "7") (name "/CA7") (class "Default")
      (node (ref "C1-6") (pin "A") (pinfunction "A_A") (pintype "passive"))
      (node (ref "C2-6") (pin "A") (pinfunction "A_A") (pintype "passive"))
      (node (ref "C3-6") (pin "A") (pinfunction "A_A") (pintype "passive"))
      (node (ref "C4-6") (pin "A") (pinfunction "A_A") (pintype "passive"))
      (node (ref "C5-6") (pin "A") (pinfunction "A_A") (pintype "passive"))
      (node (ref "C6-6") (pin "A") (pinfunction "A_A") (pintype "passive"))
      (node (ref "C7-1") (pin "C") (pinfunction "C_C") (pintype "passive"))
      (node (ref "C7-2") (pin "C") (pinfunction "C_C") (pintype "passive"))
      (node (ref "C7-3") (pin "C") (pinfunction "C_C") (pintype "passive"))
      (node (ref "C7-4") (pin "C") (pinfunction "C_C") (pintype "passive"))
      (node (ref "C7-5") (pin "C") (pinfunction "C_C") (pintype "passive"))
      (node (ref "C7-6") (pin "C") (pinfunction "C_C") (pintype "passive"))
      (node (ref "C7-7") (pin "C") (pinfunction "C_C") (pintype "passive"))
      (node (ref "C7-8") (pin "C") (pinfunction "C_C") (pintype "passive"))
      (node (ref "C8-7") (pin "A") (pinfunction "A_A") (pintype "passive"))
      (node (ref "C9-7") (pin "A") (pinfunction "A_A") (pintype "passive"))
      (node (ref "JP1") (pin "7") (pinfunction "7_7") (pintype "passive"))
    )
    (net (code "8") (name "/CA8") (class "Default")
      (node (ref "C1-7") (pin "A") (pinfunction "A_A") (pintype "passive"))
      (node (ref "C2-7") (pin "A") (pinfunction "A_A") (pintype "passive"))
      (node (ref "C3-7") (pin "A") (pinfunction "A_A") (pintype "passive"))
      (node (ref "C4-7") (pin "A") (pinfunction "A_A") (pintype "passive"))
      (node (ref "C5-7") (pin "A") (pinfunction "A_A") (pintype "passive"))
      (node (ref "C6-7") (pin "A") (pinfunction "A_A") (pintype "passive"))
      (node (ref "C7-7") (pin "A") (pinfunction "A_A") (pintype "passive"))
      (node (ref "C8-1") (pin "C") (pinfunction "C_C") (pintype "passive"))
      (node (ref "C8-2") (pin "C") (pinfunction "C_C") (pintype "passive"))
      (node (ref "C8-3") (pin "C") (pinfunction "C_C") (pintype "passive"))
      (node (ref "C8-4") (pin "C") (pinfunction "C_C") (pintype "passive"))
      (node (ref "C8-5") (pin "C") (pinfunction "C_C") (pintype "passive"))
      (node (ref "C8-6") (pin "C") (pinfunction "C_C") (pintype "passive"))
      (node (ref "C8-7") (pin "C") (pinfunction "C_C") (pintype "passive"))
      (node (ref "C8-8") (pin "C") (pinfunction "C_C") (pintype "passive"))
      (node (ref "C9-8") (pin "A") (pinfunction "A_A") (pintype "passive"))
      (node (ref "JP1") (pin "8") (pinfunction "8_8") (pintype "passive"))
    )
    (net (code "9") (name "/CA9") (class "Default")
      (node (ref "C1-8") (pin "A") (pinfunction "A_A") (pintype "passive"))
      (node (ref "C2-8") (pin "A") (pinfunction "A_A") (pintype "passive"))
      (node (ref "C3-8") (pin "A") (pinfunction "A_A") (pintype "passive"))
      (node (ref "C4-8") (pin "A") (pinfunction "A_A") (pintype "passive"))
      (node (ref "C5-8") (pin "A") (pinfunction "A_A") (pintype "passive"))
      (node (ref "C6-8") (pin "A") (pinfunction "A_A") (pintype "passive"))
      (node (ref "C7-8") (pin "A") (pinfunction "A_A") (pintype "passive"))
      (node (ref "C8-8") (pin "A") (pinfunction "A_A") (pintype "passive"))
      (node (ref "C9-1") (pin "C") (pinfunction "C_C") (pintype "passive"))
      (node (ref "C9-2") (pin "C") (pinfunction "C_C") (pintype "passive"))
      (node (ref "C9-3") (pin "C") (pinfunction "C_C") (pintype "passive"))
      (node (ref "C9-4") (pin "C") (pinfunction "C_C") (pintype "passive"))
      (node (ref "C9-5") (pin "C") (pinfunction "C_C") (pintype "passive"))
      (node (ref "C9-6") (pin "C") (pinfunction "C_C") (pintype "passive"))
      (node (ref "C9-7") (pin "C") (pinfunction "C_C") (pintype "passive"))
      (node (ref "C9-8") (pin "C") (pinfunction "C_C") (pintype "passive"))
      (node (ref "JP1") (pin "9") (pinfunction "9_9") (pintype "passive"))
    )
    (net (code "10") (name "/CB1") (class "Default")
      (node (ref "C1-10") (pin "C") (pinfunction "C_C") (pintype "passive"))
      (node (ref "C1-11") (pin "C") (pinfunction "C_C") (pintype "passive"))
      (node (ref "C1-12") (pin "C") (pinfunction "C_C") (pintype "passive"))
      (node (ref "C1-13") (pin "C") (pinfunction "C_C") (pintype "passive"))
      (node (ref "C1-14") (pin "C") (pinfunction "C_C") (pintype "passive"))
      (node (ref "C1-15") (pin "C") (pinfunction "C_C") (pintype "passive"))
      (node (ref "C1-16") (pin "C") (pinfunction "C_C") (pintype "passive"))
      (node (ref "C1-9") (pin "C") (pinfunction "C_C") (pintype "passive"))
      (node (ref "C2-9") (pin "A") (pinfunction "A_A") (pintype "passive"))
      (node (ref "C3-9") (pin "A") (pinfunction "A_A") (pintype "passive"))
      (node (ref "C4-9") (pin "A") (pinfunction "A_A") (pintype "passive"))
      (node (ref "C5-9") (pin "A") (pinfunction "A_A") (pintype "passive"))
      (node (ref "C6-9") (pin "A") (pinfunction "A_A") (pintype "passive"))
      (node (ref "C7-9") (pin "A") (pinfunction "A_A") (pintype "passive"))
      (node (ref "C8-9") (pin "A") (pinfunction "A_A") (pintype "passive"))
      (node (ref "C9-9") (pin "A") (pinfunction "A_A") (pintype "passive"))
      (node (ref "JP4") (pin "5") (pinfunction "5_5") (pintype "passive"))
    )
    (net (code "11") (name "/CB2") (class "Default")
      (node (ref "C1-9") (pin "A") (pinfunction "A_A") (pintype "passive"))
      (node (ref "C2-10") (pin "C") (pinfunction "C_C") (pintype "passive"))
      (node (ref "C2-11") (pin "C") (pinfunction "C_C") (pintype "passive"))
      (node (ref "C2-12") (pin "C") (pinfunction "C_C") (pintype "passive"))
      (node (ref "C2-13") (pin "C") (pinfunction "C_C") (pintype "passive"))
      (node (ref "C2-14") (pin "C") (pinfunction "C_C") (pintype "passive"))
      (node (ref "C2-15") (pin "C") (pinfunction "C_C") (pintype "passive"))
      (node (ref "C2-16") (pin "C") (pinfunction "C_C") (pintype "passive"))
      (node (ref "C2-9") (pin "C") (pinfunction "C_C") (pintype "passive"))
      (node (ref "C3-10") (pin "A") (pinfunction "A_A") (pintype "passive"))
      (node (ref "C4-10") (pin "A") (pinfunction "A_A") (pintype "passive"))
      (node (ref "C5-10") (pin "A") (pinfunction "A_A") (pintype "passive"))
      (node (ref "C6-10") (pin "A") (pinfunction "A_A") (pintype "passive"))
      (node (ref "C7-10") (pin "A") (pinfunction "A_A") (pintype "passive"))
      (node (ref "C8-10") (pin "A") (pinfunction "A_A") (pintype "passive"))
      (node (ref "C9-10") (pin "A") (pinfunction "A_A") (pintype "passive"))
      (node (ref "JP4") (pin "6") (pinfunction "6_6") (pintype "passive"))
    )
    (net (code "12") (name "/CB3") (class "Default")
      (node (ref "C1-10") (pin "A") (pinfunction "A_A") (pintype "passive"))
      (node (ref "C2-10") (pin "A") (pinfunction "A_A") (pintype "passive"))
      (node (ref "C3-10") (pin "C") (pinfunction "C_C") (pintype "passive"))
      (node (ref "C3-11") (pin "C") (pinfunction "C_C") (pintype "passive"))
      (node (ref "C3-12") (pin "C") (pinfunction "C_C") (pintype "passive"))
      (node (ref "C3-13") (pin "C") (pinfunction "C_C") (pintype "passive"))
      (node (ref "C3-14") (pin "C") (pinfunction "C_C") (pintype "passive"))
      (node (ref "C3-15") (pin "C") (pinfunction "C_C") (pintype "passive"))
      (node (ref "C3-16") (pin "C") (pinfunction "C_C") (pintype "passive"))
      (node (ref "C3-9") (pin "C") (pinfunction "C_C") (pintype "passive"))
      (node (ref "C4-11") (pin "A") (pinfunction "A_A") (pintype "passive"))
      (node (ref "C5-11") (pin "A") (pinfunction "A_A") (pintype "passive"))
      (node (ref "C6-11") (pin "A") (pinfunction "A_A") (pintype "passive"))
      (node (ref "C7-11") (pin "A") (pinfunction "A_A") (pintype "passive"))
      (node (ref "C8-11") (pin "A") (pinfunction "A_A") (pintype "passive"))
      (node (ref "C9-11") (pin "A") (pinfunction "A_A") (pintype "passive"))
      (node (ref "JP4") (pin "7") (pinfunction "7_7") (pintype "passive"))
    )
    (net (code "13") (name "/CB4") (class "Default")
      (node (ref "C1-11") (pin "A") (pinfunction "A_A") (pintype "passive"))
      (node (ref "C2-11") (pin "A") (pinfunction "A_A") (pintype "passive"))
      (node (ref "C3-11") (pin "A") (pinfunction "A_A") (pintype "passive"))
      (node (ref "C4-10") (pin "C") (pinfunction "C_C") (pintype "passive"))
      (node (ref "C4-11") (pin "C") (pinfunction "C_C") (pintype "passive"))
      (node (ref "C4-12") (pin "C") (pinfunction "C_C") (pintype "passive"))
      (node (ref "C4-13") (pin "C") (pinfunction "C_C") (pintype "passive"))
      (node (ref "C4-14") (pin "C") (pinfunction "C_C") (pintype "passive"))
      (node (ref "C4-15") (pin "C") (pinfunction "C_C") (pintype "passive"))
      (node (ref "C4-16") (pin "C") (pinfunction "C_C") (pintype "passive"))
      (node (ref "C4-9") (pin "C") (pinfunction "C_C") (pintype "passive"))
      (node (ref "C5-12") (pin "A") (pinfunction "A_A") (pintype "passive"))
      (node (ref "C6-12") (pin "A") (pinfunction "A_A") (pintype "passive"))
      (node (ref "C7-12") (pin "A") (pinfunction "A_A") (pintype "passive"))
      (node (ref "C8-12") (pin "A") (pinfunction "A_A") (pintype "passive"))
      (node (ref "C9-12") (pin "A") (pinfunction "A_A") (pintype "passive"))
      (node (ref "JP4") (pin "8") (pinfunction "8_8") (pintype "passive"))
    )
    (net (code "14") (name "/CB5") (class "Default")
      (node (ref "C1-12") (pin "A") (pinfunction "A_A") (pintype "passive"))
      (node (ref "C2-12") (pin "A") (pinfunction "A_A") (pintype "passive"))
      (node (ref "C3-12") (pin "A") (pinfunction "A_A") (pintype "passive"))
      (node (ref "C4-12") (pin "A") (pinfunction "A_A") (pintype "passive"))
      (node (ref "C5-10") (pin "C") (pinfunction "C_C") (pintype "passive"))
      (node (ref "C5-11") (pin "C") (pinfunction "C_C") (pintype "passive"))
      (node (ref "C5-12") (pin "C") (pinfunction "C_C") (pintype "passive"))
      (node (ref "C5-13") (pin "C") (pinfunction "C_C") (pintype "passive"))
      (node (ref "C5-14") (pin "C") (pinfunction "C_C") (pintype "passive"))
      (node (ref "C5-15") (pin "C") (pinfunction "C_C") (pintype "passive"))
      (node (ref "C5-16") (pin "C") (pinfunction "C_C") (pintype "passive"))
      (node (ref "C5-9") (pin "C") (pinfunction "C_C") (pintype "passive"))
      (node (ref "C6-13") (pin "A") (pinfunction "A_A") (pintype "passive"))
      (node (ref "C7-13") (pin "A") (pinfunction "A_A") (pintype "passive"))
      (node (ref "C8-13") (pin "A") (pinfunction "A_A") (pintype "passive"))
      (node (ref "C9-13") (pin "A") (pinfunction "A_A") (pintype "passive"))
      (node (ref "JP4") (pin "9") (pinfunction "9_9") (pintype "passive"))
    )
    (net (code "15") (name "/CB6") (class "Default")
      (node (ref "C1-13") (pin "A") (pinfunction "A_A") (pintype "passive"))
      (node (ref "C2-13") (pin "A") (pinfunction "A_A") (pintype "passive"))
      (node (ref "C3-13") (pin "A") (pinfunction "A_A") (pintype "passive"))
      (node (ref "C4-13") (pin "A") (pinfunction "A_A") (pintype "passive"))
      (node (ref "C5-13") (pin "A") (pinfunction "A_A") (pintype "passive"))
      (node (ref "C6-10") (pin "C") (pinfunction "C_C") (pintype "passive"))
      (node (ref "C6-11") (pin "C") (pinfunction "C_C") (pintype "passive"))
      (node (ref "C6-12") (pin "C") (pinfunction "C_C") (pintype "passive"))
      (node (ref "C6-13") (pin "C") (pinfunction "C_C") (pintype "passive"))
      (node (ref "C6-14") (pin "C") (pinfunction "C_C") (pintype "passive"))
      (node (ref "C6-15") (pin "C") (pinfunction "C_C") (pintype "passive"))
      (node (ref "C6-16") (pin "C") (pinfunction "C_C") (pintype "passive"))
      (node (ref "C6-9") (pin "C") (pinfunction "C_C") (pintype "passive"))
      (node (ref "C7-14") (pin "A") (pinfunction "A_A") (pintype "passive"))
      (node (ref "C8-14") (pin "A") (pinfunction "A_A") (pintype "passive"))
      (node (ref "C9-14") (pin "A") (pinfunction "A_A") (pintype "passive"))
      (node (ref "JP4") (pin "10") (pinfunction "10_10") (pintype "passive"))
    )
    (net (code "16") (name "/CB7") (class "Default")
      (node (ref "C1-14") (pin "A") (pinfunction "A_A") (pintype "passive"))
      (node (ref "C2-14") (pin "A") (pinfunction "A_A") (pintype "passive"))
      (node (ref "C3-14") (pin "A") (pinfunction "A_A") (pintype "passive"))
      (node (ref "C4-14") (pin "A") (pinfunction "A_A") (pintype "passive"))
      (node (ref "C5-14") (pin "A") (pinfunction "A_A") (pintype "passive"))
      (node (ref "C6-14") (pin "A") (pinfunction "A_A") (pintype "passive"))
      (node (ref "C7-10") (pin "C") (pinfunction "C_C") (pintype "passive"))
      (node (ref "C7-11") (pin "C") (pinfunction "C_C") (pintype "passive"))
      (node (ref "C7-12") (pin "C") (pinfunction "C_C") (pintype "passive"))
      (node (ref "C7-13") (pin "C") (pinfunction "C_C") (pintype "passive"))
      (node (ref "C7-14") (pin "C") (pinfunction "C_C") (pintype "passive"))
      (node (ref "C7-15") (pin "C") (pinfunction "C_C") (pintype "passive"))
      (node (ref "C7-16") (pin "C") (pinfunction "C_C") (pintype "passive"))
      (node (ref "C7-9") (pin "C") (pinfunction "C_C") (pintype "passive"))
      (node (ref "C8-15") (pin "A") (pinfunction "A_A") (pintype "passive"))
      (node (ref "C9-15") (pin "A") (pinfunction "A_A") (pintype "passive"))
      (node (ref "JP4") (pin "11") (pinfunction "11_11") (pintype "passive"))
    )
    (net (code "17") (name "/CB8") (class "Default")
      (node (ref "C1-15") (pin "A") (pinfunction "A_A") (pintype "passive"))
      (node (ref "C2-15") (pin "A") (pinfunction "A_A") (pintype "passive"))
      (node (ref "C3-15") (pin "A") (pinfunction "A_A") (pintype "passive"))
      (node (ref "C4-15") (pin "A") (pinfunction "A_A") (pintype "passive"))
      (node (ref "C5-15") (pin "A") (pinfunction "A_A") (pintype "passive"))
      (node (ref "C6-15") (pin "A") (pinfunction "A_A") (pintype "passive"))
      (node (ref "C7-15") (pin "A") (pinfunction "A_A") (pintype "passive"))
      (node (ref "C8-10") (pin "C") (pinfunction "C_C") (pintype "passive"))
      (node (ref "C8-11") (pin "C") (pinfunction "C_C") (pintype "passive"))
      (node (ref "C8-12") (pin "C") (pinfunction "C_C") (pintype "passive"))
      (node (ref "C8-13") (pin "C") (pinfunction "C_C") (pintype "passive"))
      (node (ref "C8-14") (pin "C") (pinfunction "C_C") (pintype "passive"))
      (node (ref "C8-15") (pin "C") (pinfunction "C_C") (pintype "passive"))
      (node (ref "C8-16") (pin "C") (pinfunction "C_C") (pintype "passive"))
      (node (ref "C8-9") (pin "C") (pinfunction "C_C") (pintype "passive"))
      (node (ref "C9-16") (pin "A") (pinfunction "A_A") (pintype "passive"))
      (node (ref "JP4") (pin "12") (pinfunction "12_12") (pintype "passive"))
    )
    (net (code "18") (name "/CB9") (class "Default")
      (node (ref "C1-16") (pin "A") (pinfunction "A_A") (pintype "passive"))
      (node (ref "C2-16") (pin "A") (pinfunction "A_A") (pintype "passive"))
      (node (ref "C3-16") (pin "A") (pinfunction "A_A") (pintype "passive"))
      (node (ref "C4-16") (pin "A") (pinfunction "A_A") (pintype "passive"))
      (node (ref "C5-16") (pin "A") (pinfunction "A_A") (pintype "passive"))
      (node (ref "C6-16") (pin "A") (pinfunction "A_A") (pintype "passive"))
      (node (ref "C7-16") (pin "A") (pinfunction "A_A") (pintype "passive"))
      (node (ref "C8-16") (pin "A") (pinfunction "A_A") (pintype "passive"))
      (node (ref "C9-10") (pin "C") (pinfunction "C_C") (pintype "passive"))
      (node (ref "C9-11") (pin "C") (pinfunction "C_C") (pintype "passive"))
      (node (ref "C9-12") (pin "C") (pinfunction "C_C") (pintype "passive"))
      (node (ref "C9-13") (pin "C") (pinfunction "C_C") (pintype "passive"))
      (node (ref "C9-14") (pin "C") (pinfunction "C_C") (pintype "passive"))
      (node (ref "C9-15") (pin "C") (pinfunction "C_C") (pintype "passive"))
      (node (ref "C9-16") (pin "C") (pinfunction "C_C") (pintype "passive"))
      (node (ref "C9-9") (pin "C") (pinfunction "C_C") (pintype "passive"))
      (node (ref "JP4") (pin "13") (pinfunction "13_13") (pintype "passive"))
    )
    (net (code "19") (name "unconnected-(JP1-Pad10)") (class "Default")
      (node (ref "JP1") (pin "10") (pinfunction "10_10") (pintype "passive"))
    )
    (net (code "20") (name "unconnected-(JP1-Pad11)") (class "Default")
      (node (ref "JP1") (pin "11") (pinfunction "11_11") (pintype "passive"))
    )
    (net (code "21") (name "unconnected-(JP1-Pad12)") (class "Default")
      (node (ref "JP1") (pin "12") (pinfunction "12_12") (pintype "passive"))
    )
    (net (code "22") (name "unconnected-(JP1-Pad13)") (class "Default")
      (node (ref "JP1") (pin "13") (pinfunction "13_13") (pintype "passive"))
    )
    (net (code "23") (name "unconnected-(JP4-Pad1)") (class "Default")
      (node (ref "JP4") (pin "1") (pinfunction "1_1") (pintype "passive"))
    )
    (net (code "24") (name "unconnected-(JP4-Pad2)") (class "Default")
      (node (ref "JP4") (pin "2") (pinfunction "2_2") (pintype "passive"))
    )
    (net (code "25") (name "unconnected-(JP4-Pad3)") (class "Default")
      (node (ref "JP4") (pin "3") (pinfunction "3_3") (pintype "passive"))
    )
    (net (code "26") (name "unconnected-(JP4-Pad4)") (class "Default")
      (node (ref "JP4") (pin "4") (pinfunction "4_4") (pintype "passive"))
    )
  )
)
